# DuoTristateBuffer.net
KiCad netlist of a schematic drawn in EAGLE
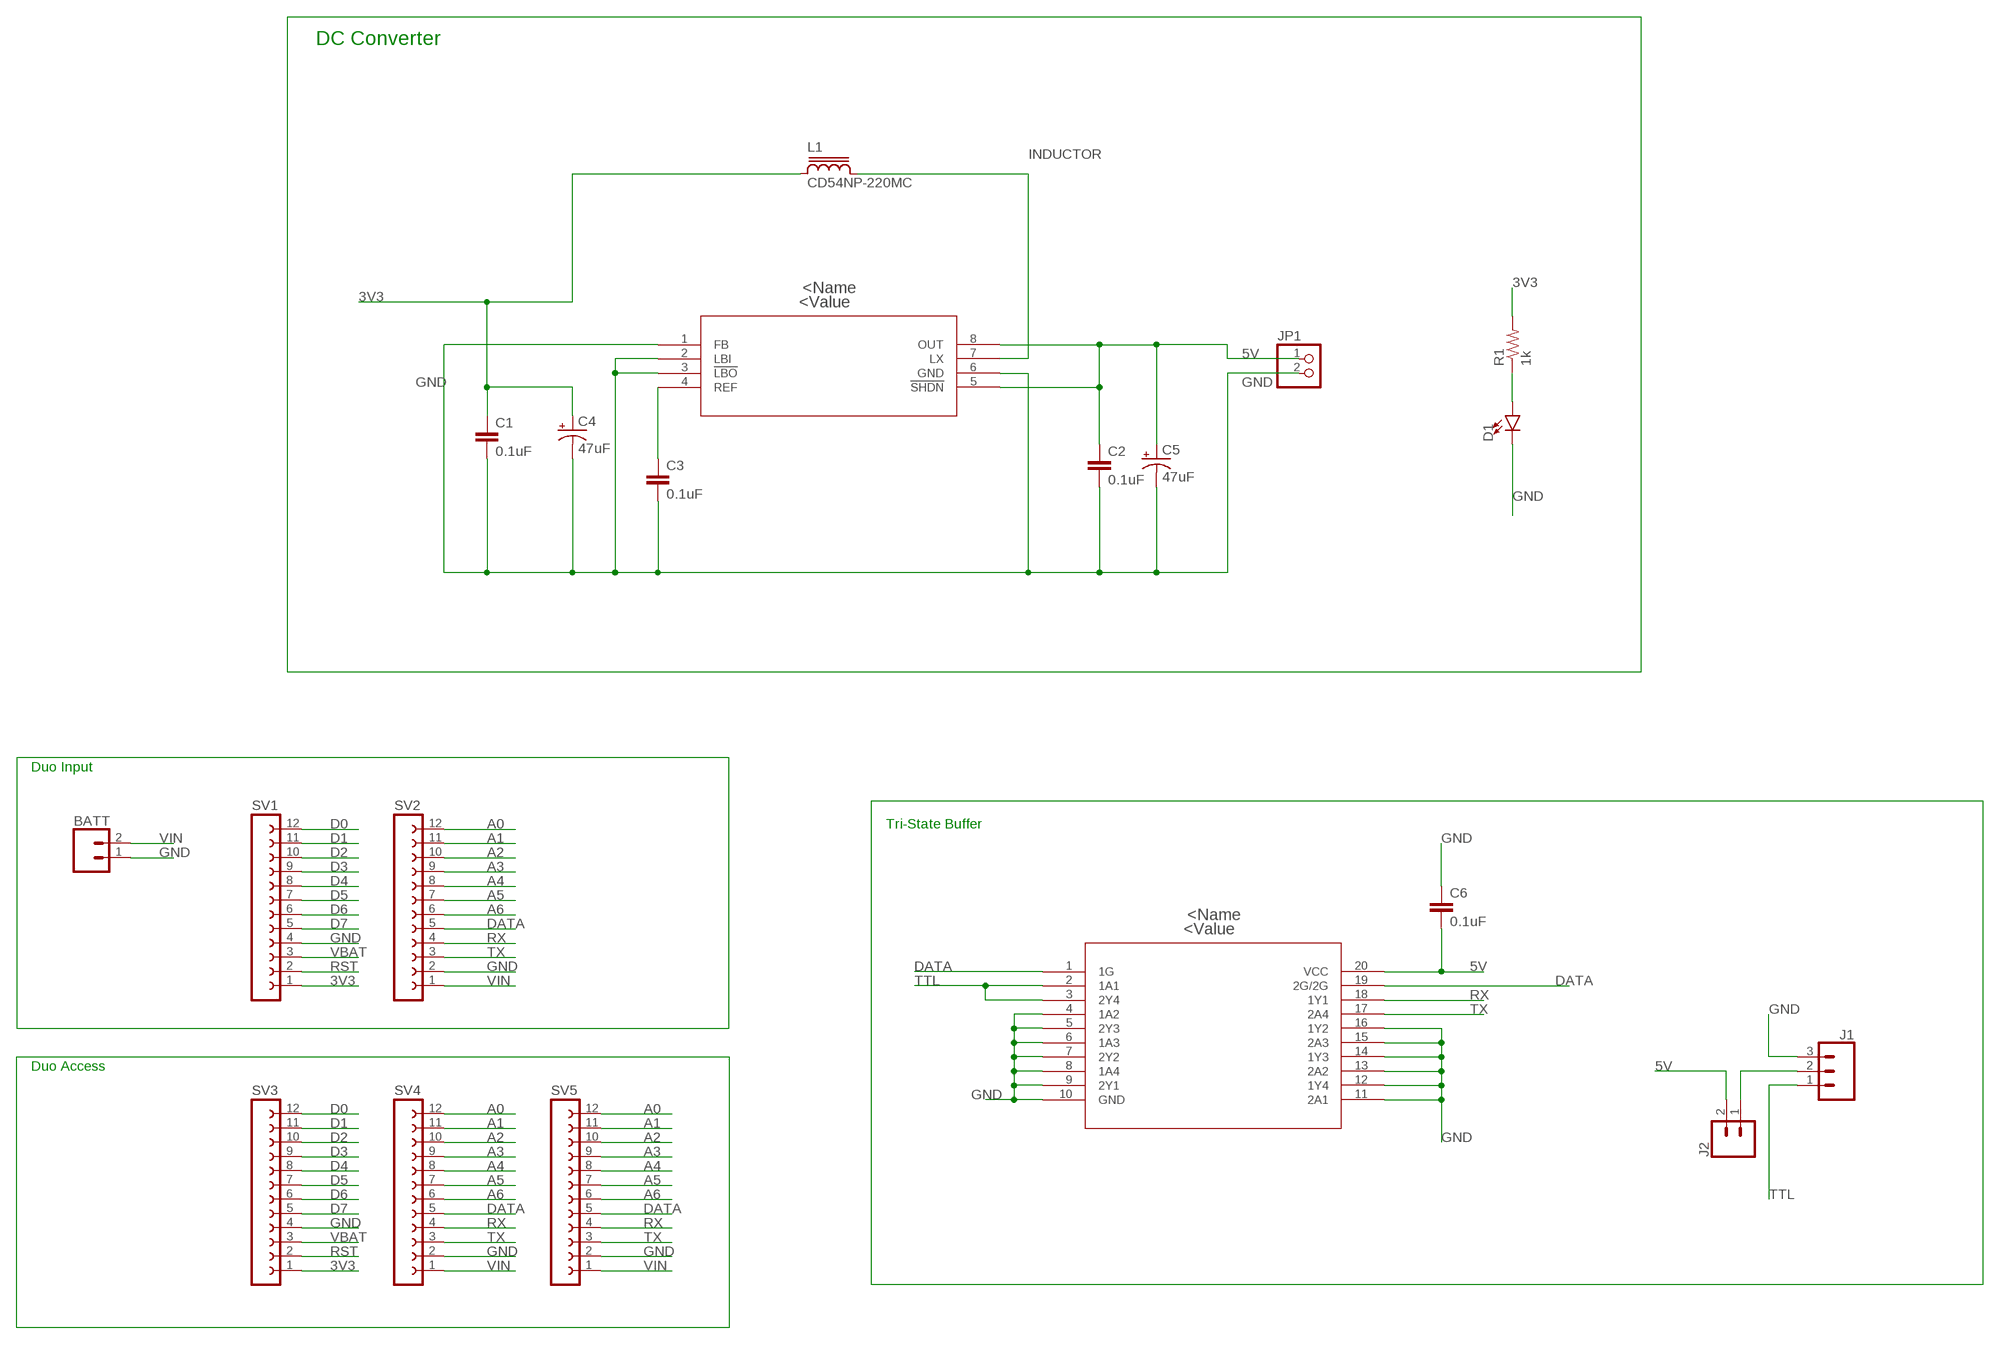
[diagram p0: schematic, sheet 1]

(export (version "E")
  (design (tool "Eeschema 10.0.6"))
  (components
    (comp (ref "BATT")
      (value "CONN_02-JST-2-PTH-NO_SILK")
      (footprint "eagle-import:JST-2-PTH-NS")
      (libsource (lib "eagle-import") (part "CONN_02-JST-2-PTH-NO_SILK"))
    )
    (comp (ref "BUFFER")
      (value "SN74LS241_DW_20DW20-M")
      (footprint "eagle-import:DW20-M")
      (libsource (lib "eagle-import") (part "SN74LS241_DW_20DW20-M"))
    )
    (comp (ref "C1")
      (value "0.1uF")
      (footprint "eagle-import:0603")
      (libsource (lib "eagle-import") (part "0.1UF-0603-25V-5%"))
    )
    (comp (ref "C2")
      (value "0.1uF")
      (footprint "eagle-import:0603")
      (libsource (lib "eagle-import") (part "0.1UF-0603-25V-5%"))
    )
    (comp (ref "C3")
      (value "0.1uF")
      (footprint "eagle-import:0603")
      (libsource (lib "eagle-import") (part "0.1UF-0603-25V-5%"))
    )
    (comp (ref "C4")
      (value "47uF")
      (footprint "eagle-import:EIA3528")
      (libsource (lib "eagle-import") (part "47UF-POLAR-EIA3528-10V-10%"))
    )
    (comp (ref "C5")
      (value "47uF")
      (footprint "eagle-import:EIA3528")
      (libsource (lib "eagle-import") (part "47UF-POLAR-EIA3528-10V-10%"))
    )
    (comp (ref "C6")
      (value "0.1uF")
      (footprint "eagle-import:0603")
      (libsource (lib "eagle-import") (part "0.1UF-0603-25V-5%"))
    )
    (comp (ref "D1")
      (value "LED3MM")
      (footprint "eagle-import:LED_3MM")
      (libsource (lib "eagle-import") (part "LED3MM"))
    )
    (comp (ref "J1")
      (value "CONN_03")
      (footprint "eagle-import:1X03")
      (libsource (lib "eagle-import") (part "CONN_03"))
    )
    (comp (ref "J2")
      (value "CONN_02")
      (footprint "eagle-import:1X02")
      (libsource (lib "eagle-import") (part "CONN_02"))
    )
    (comp (ref "JP1")
      (value "PINHD-1X2/90")
      (footprint "eagle-import:1X02_90")
      (libsource (lib "eagle-import") (part "PINHD-1X2/90"))
    )
    (comp (ref "L1")
      (value "CD54NP-220MC")
      (footprint "eagle-import:CD54")
      (libsource (lib "eagle-import") (part "CD54"))
    )
    (comp (ref "R1")
      (value "1k")
      (footprint "eagle-import:R2010")
      (libsource (lib "eagle-import") (part "R-US_R2010"))
    )
    (comp (ref "SV1")
      (value "FE12-1")
      (footprint "eagle-import:FE12")
      (libsource (lib "eagle-import") (part "FE12-1"))
    )
    (comp (ref "SV2")
      (value "FE12-1")
      (footprint "eagle-import:FE12")
      (libsource (lib "eagle-import") (part "FE12-1"))
    )
    (comp (ref "SV3")
      (value "FE12-1")
      (footprint "eagle-import:FE12")
      (libsource (lib "eagle-import") (part "FE12-1"))
    )
    (comp (ref "SV4")
      (value "FE12-1")
      (footprint "eagle-import:FE12")
      (libsource (lib "eagle-import") (part "FE12-1"))
    )
    (comp (ref "SV5")
      (value "FE12-1")
      (footprint "eagle-import:FE12")
      (libsource (lib "eagle-import") (part "FE12-1"))
    )
    (comp (ref "U1")
      (value "MAX1674EUA+T")
      (footprint "eagle-import:21-0036K")
      (libsource (lib "eagle-import") (part "MAX1674EUA+T"))
    )
  )
  (nets
    (net (code "1") (name "/3V3") (class "Default")
      (node (ref "C1") (pin "1") (pinfunction "1_1") (pintype "passive"))
      (node (ref "C4") (pin "A") (pinfunction "+_A") (pintype "passive"))
      (node (ref "L1") (pin "1") (pinfunction "1_1") (pintype "passive"))
      (node (ref "R1") (pin "2") (pinfunction "2_2") (pintype "passive"))
      (node (ref "SV1") (pin "1") (pinfunction "1_1") (pintype "passive"))
      (node (ref "SV3") (pin "1") (pinfunction "1_1") (pintype "passive"))
    )
    (net (code "2") (name "/5V") (class "Default")
      (node (ref "BUFFER") (pin "20") (pinfunction "VCC_20") (pintype "power_in"))
      (node (ref "C2") (pin "1") (pinfunction "1_1") (pintype "passive"))
      (node (ref "C5") (pin "A") (pinfunction "+_A") (pintype "passive"))
      (node (ref "C6") (pin "2") (pinfunction "2_2") (pintype "passive"))
      (node (ref "J2") (pin "2") (pinfunction "2_2") (pintype "passive"))
      (node (ref "JP1") (pin "1") (pinfunction "1_1") (pintype "passive"))
      (node (ref "U1") (pin "5") (pinfunction "~{SHDN}_5") (pintype "bidirectional"))
      (node (ref "U1") (pin "8") (pinfunction "OUT_8") (pintype "output"))
    )
    (net (code "3") (name "/A0") (class "Default")
      (node (ref "SV2") (pin "12") (pinfunction "12_12") (pintype "passive"))
      (node (ref "SV4") (pin "12") (pinfunction "12_12") (pintype "passive"))
      (node (ref "SV5") (pin "12") (pinfunction "12_12") (pintype "passive"))
    )
    (net (code "4") (name "/A1") (class "Default")
      (node (ref "SV2") (pin "11") (pinfunction "11_11") (pintype "passive"))
      (node (ref "SV4") (pin "11") (pinfunction "11_11") (pintype "passive"))
      (node (ref "SV5") (pin "11") (pinfunction "11_11") (pintype "passive"))
    )
    (net (code "5") (name "/A2") (class "Default")
      (node (ref "SV2") (pin "10") (pinfunction "10_10") (pintype "passive"))
      (node (ref "SV4") (pin "10") (pinfunction "10_10") (pintype "passive"))
      (node (ref "SV5") (pin "10") (pinfunction "10_10") (pintype "passive"))
    )
    (net (code "6") (name "/A3") (class "Default")
      (node (ref "SV2") (pin "9") (pinfunction "9_9") (pintype "passive"))
      (node (ref "SV4") (pin "9") (pinfunction "9_9") (pintype "passive"))
      (node (ref "SV5") (pin "9") (pinfunction "9_9") (pintype "passive"))
    )
    (net (code "7") (name "/A4") (class "Default")
      (node (ref "SV2") (pin "8") (pinfunction "8_8") (pintype "passive"))
      (node (ref "SV4") (pin "8") (pinfunction "8_8") (pintype "passive"))
      (node (ref "SV5") (pin "8") (pinfunction "8_8") (pintype "passive"))
    )
    (net (code "8") (name "/A5") (class "Default")
      (node (ref "SV2") (pin "7") (pinfunction "7_7") (pintype "passive"))
      (node (ref "SV4") (pin "7") (pinfunction "7_7") (pintype "passive"))
      (node (ref "SV5") (pin "7") (pinfunction "7_7") (pintype "passive"))
    )
    (net (code "9") (name "/A6") (class "Default")
      (node (ref "SV2") (pin "6") (pinfunction "6_6") (pintype "passive"))
      (node (ref "SV4") (pin "6") (pinfunction "6_6") (pintype "passive"))
      (node (ref "SV5") (pin "6") (pinfunction "6_6") (pintype "passive"))
    )
    (net (code "10") (name "/D0") (class "Default")
      (node (ref "SV1") (pin "12") (pinfunction "12_12") (pintype "passive"))
      (node (ref "SV3") (pin "12") (pinfunction "12_12") (pintype "passive"))
    )
    (net (code "11") (name "/D1") (class "Default")
      (node (ref "SV1") (pin "11") (pinfunction "11_11") (pintype "passive"))
      (node (ref "SV3") (pin "11") (pinfunction "11_11") (pintype "passive"))
    )
    (net (code "12") (name "/D2") (class "Default")
      (node (ref "SV1") (pin "10") (pinfunction "10_10") (pintype "passive"))
      (node (ref "SV3") (pin "10") (pinfunction "10_10") (pintype "passive"))
    )
    (net (code "13") (name "/D3") (class "Default")
      (node (ref "SV1") (pin "9") (pinfunction "9_9") (pintype "passive"))
      (node (ref "SV3") (pin "9") (pinfunction "9_9") (pintype "passive"))
    )
    (net (code "14") (name "/D4") (class "Default")
      (node (ref "SV1") (pin "8") (pinfunction "8_8") (pintype "passive"))
      (node (ref "SV3") (pin "8") (pinfunction "8_8") (pintype "passive"))
    )
    (net (code "15") (name "/D5") (class "Default")
      (node (ref "SV1") (pin "7") (pinfunction "7_7") (pintype "passive"))
      (node (ref "SV3") (pin "7") (pinfunction "7_7") (pintype "passive"))
    )
    (net (code "16") (name "/D6") (class "Default")
      (node (ref "SV1") (pin "6") (pinfunction "6_6") (pintype "passive"))
      (node (ref "SV3") (pin "6") (pinfunction "6_6") (pintype "passive"))
    )
    (net (code "17") (name "/D7") (class "Default")
      (node (ref "SV1") (pin "5") (pinfunction "5_5") (pintype "passive"))
      (node (ref "SV3") (pin "5") (pinfunction "5_5") (pintype "passive"))
    )
    (net (code "18") (name "/DATA") (class "Default")
      (node (ref "BUFFER") (pin "1") (pinfunction "1G_1") (pintype "input"))
      (node (ref "BUFFER") (pin "19") (pinfunction "2G/2G_19") (pintype "input"))
      (node (ref "SV2") (pin "5") (pinfunction "5_5") (pintype "passive"))
      (node (ref "SV4") (pin "5") (pinfunction "5_5") (pintype "passive"))
      (node (ref "SV5") (pin "5") (pinfunction "5_5") (pintype "passive"))
    )
    (net (code "19") (name "/GND") (class "Default")
      (node (ref "BATT") (pin "1") (pinfunction "1_1") (pintype "passive"))
      (node (ref "BUFFER") (pin "10") (pinfunction "GND_10") (pintype "power_in"))
      (node (ref "BUFFER") (pin "11") (pinfunction "2A1_11") (pintype "input"))
      (node (ref "BUFFER") (pin "12") (pinfunction "1Y4_12") (pintype "output"))
      (node (ref "BUFFER") (pin "13") (pinfunction "2A2_13") (pintype "input"))
      (node (ref "BUFFER") (pin "14") (pinfunction "1Y3_14") (pintype "output"))
      (node (ref "BUFFER") (pin "15") (pinfunction "2A3_15") (pintype "input"))
      (node (ref "BUFFER") (pin "16") (pinfunction "1Y2_16") (pintype "output"))
      (node (ref "BUFFER") (pin "4") (pinfunction "1A2_4") (pintype "input"))
      (node (ref "BUFFER") (pin "5") (pinfunction "2Y3_5") (pintype "output"))
      (node (ref "BUFFER") (pin "6") (pinfunction "1A3_6") (pintype "input"))
      (node (ref "BUFFER") (pin "7") (pinfunction "2Y2_7") (pintype "output"))
      (node (ref "BUFFER") (pin "8") (pinfunction "1A4_8") (pintype "input"))
      (node (ref "BUFFER") (pin "9") (pinfunction "2Y1_9") (pintype "output"))
      (node (ref "C1") (pin "2") (pinfunction "2_2") (pintype "passive"))
      (node (ref "C2") (pin "2") (pinfunction "2_2") (pintype "passive"))
      (node (ref "C3") (pin "2") (pinfunction "2_2") (pintype "passive"))
      (node (ref "C4") (pin "C") (pinfunction "-_C") (pintype "passive"))
      (node (ref "C5") (pin "C") (pinfunction "-_C") (pintype "passive"))
      (node (ref "C6") (pin "1") (pinfunction "1_1") (pintype "passive"))
      (node (ref "D1") (pin "K") (pinfunction "C_K") (pintype "passive"))
      (node (ref "J1") (pin "3") (pinfunction "3_3") (pintype "passive"))
      (node (ref "JP1") (pin "2") (pinfunction "2_2") (pintype "passive"))
      (node (ref "SV1") (pin "4") (pinfunction "4_4") (pintype "passive"))
      (node (ref "SV2") (pin "2") (pinfunction "2_2") (pintype "passive"))
      (node (ref "SV3") (pin "4") (pinfunction "4_4") (pintype "passive"))
      (node (ref "SV4") (pin "2") (pinfunction "2_2") (pintype "passive"))
      (node (ref "SV5") (pin "2") (pinfunction "2_2") (pintype "passive"))
      (node (ref "U1") (pin "1") (pinfunction "FB_1") (pintype "bidirectional"))
      (node (ref "U1") (pin "2") (pinfunction "LBI_2") (pintype "bidirectional"))
      (node (ref "U1") (pin "3") (pinfunction "~{LBO}_3") (pintype "bidirectional"))
      (node (ref "U1") (pin "6") (pinfunction "GND_6") (pintype "power_in"))
    )
    (net (code "20") (name "/INDUCTOR") (class "Default")
      (node (ref "L1") (pin "2") (pinfunction "2_2") (pintype "passive"))
      (node (ref "U1") (pin "7") (pinfunction "LX_7") (pintype "bidirectional"))
    )
    (net (code "21") (name "/RST") (class "Default")
      (node (ref "SV1") (pin "2") (pinfunction "2_2") (pintype "passive"))
      (node (ref "SV3") (pin "2") (pinfunction "2_2") (pintype "passive"))
    )
    (net (code "22") (name "/RX") (class "Default")
      (node (ref "BUFFER") (pin "18") (pinfunction "1Y1_18") (pintype "output"))
      (node (ref "SV2") (pin "4") (pinfunction "4_4") (pintype "passive"))
      (node (ref "SV4") (pin "4") (pinfunction "4_4") (pintype "passive"))
      (node (ref "SV5") (pin "4") (pinfunction "4_4") (pintype "passive"))
    )
    (net (code "23") (name "/TTL") (class "Default")
      (node (ref "BUFFER") (pin "2") (pinfunction "1A1_2") (pintype "input"))
      (node (ref "BUFFER") (pin "3") (pinfunction "2Y4_3") (pintype "output"))
      (node (ref "J1") (pin "1") (pinfunction "1_1") (pintype "passive"))
    )
    (net (code "24") (name "/TX") (class "Default")
      (node (ref "BUFFER") (pin "17") (pinfunction "2A4_17") (pintype "input"))
      (node (ref "SV2") (pin "3") (pinfunction "3_3") (pintype "passive"))
      (node (ref "SV4") (pin "3") (pinfunction "3_3") (pintype "passive"))
      (node (ref "SV5") (pin "3") (pinfunction "3_3") (pintype "passive"))
    )
    (net (code "25") (name "/VBAT") (class "Default")
      (node (ref "SV1") (pin "3") (pinfunction "3_3") (pintype "passive"))
      (node (ref "SV3") (pin "3") (pinfunction "3_3") (pintype "passive"))
    )
    (net (code "26") (name "/VIN") (class "Default")
      (node (ref "BATT") (pin "2") (pinfunction "2_2") (pintype "passive"))
      (node (ref "SV2") (pin "1") (pinfunction "1_1") (pintype "passive"))
      (node (ref "SV4") (pin "1") (pinfunction "1_1") (pintype "passive"))
      (node (ref "SV5") (pin "1") (pinfunction "1_1") (pintype "passive"))
    )
    (net (code "27") (name "Net-(D1-PadA)") (class "Default")
      (node (ref "D1") (pin "A") (pinfunction "A_A") (pintype "passive"))
      (node (ref "R1") (pin "1") (pinfunction "1_1") (pintype "passive"))
    )
    (net (code "28") (name "Net-(J1-Pad2)") (class "Default")
      (node (ref "J1") (pin "2") (pinfunction "2_2") (pintype "passive"))
      (node (ref "J2") (pin "1") (pinfunction "1_1") (pintype "passive"))
    )
    (net (code "29") (name "Net-(U1-REF)") (class "Default")
      (node (ref "C3") (pin "1") (pinfunction "1_1") (pintype "passive"))
      (node (ref "U1") (pin "4") (pinfunction "REF_4") (pintype "bidirectional"))
    )
  )
)
